# Schematic.net
KiCad netlist of a schematic drawn in Altium Designer
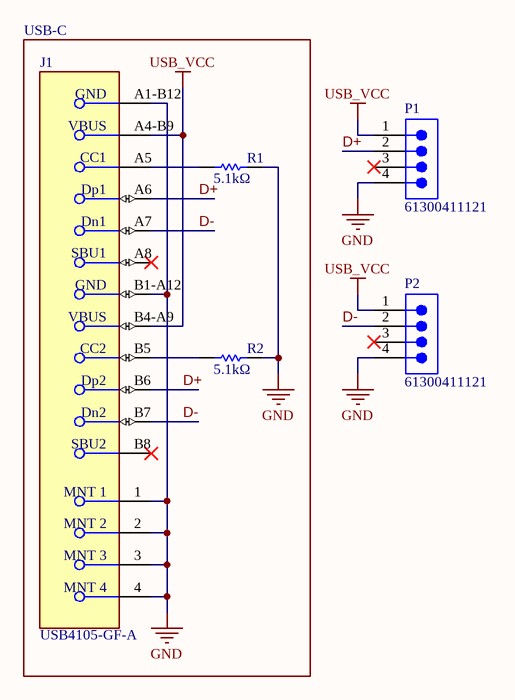
[diagram p0: Schematic.SchDoc]

(export (version "E")
  (design (tool "Eeschema 10.0.6"))
  (components
    (comp (ref "J1")
      (value "USB4105-GF-A")
      (footprint "FP-USB4105-GF-A-MFG")
      (description "CONN RCPT USB2.0 TYPEC 5A")
      (fields
        (field (name "MANUFACTURER") "GCT")
        (field (name "OCTOPART") "https://octopart.com/usb4105-gf-a-gct-106627878")
      )
      (libsource (lib "Altium Content Vault") (part "e7c17a616881a82b79941196b4bec10"))
    )
    (comp (ref "P1")
      (value "61300411121")
      (footprint "61300411121")
      (libsource (lib "Altium Content Vault") (part "Header_Male_1R_04P"))
    )
    (comp (ref "P2")
      (value "61300411121")
      (footprint "61300411121")
      (libsource (lib "Altium Content Vault") (part "Header_Male_1R_04P"))
    )
    (comp (ref "R1")
      (value "5.1kΩ")
      (footprint "RESC3116X65X40LL10T20")
      (fields (field (name "MANUFACTURER") "Yageo") (field (name "PART NUMBER") "RC1206JR-075K1L"))
      (libsource (lib "Altium Content Vault") (part "RES"))
    )
    (comp (ref "R2")
      (value "5.1kΩ")
      (footprint "RESC3116X65X40LL10T20")
      (fields (field (name "MANUFACTURER") "Yageo") (field (name "PART NUMBER") "RC1206JR-075K1L"))
      (libsource (lib "Altium Content Vault") (part "RES"))
    )
  )
  (nets
    (net (code "1") (name "/D+") (class "Default")
      (node (ref "J1") (pin "A6") (pinfunction "Dp1_A6") (pintype "bidirectional"))
      (node (ref "J1") (pin "B6") (pinfunction "Dp2_B6") (pintype "bidirectional"))
      (node (ref "P1") (pin "2") (pinfunction "2_2") (pintype "passive"))
    )
    (net (code "2") (name "/D-") (class "Default")
      (node (ref "J1") (pin "A7") (pinfunction "Dn1_A7") (pintype "bidirectional"))
      (node (ref "J1") (pin "B7") (pinfunction "Dn2_B7") (pintype "bidirectional"))
      (node (ref "P2") (pin "2") (pinfunction "2_2") (pintype "passive"))
    )
    (net (code "3") (name "GND") (class "Default")
      (node (ref "J1") (pin "1") (pinfunction "MNT_1_1") (pintype "power_in"))
      (node (ref "J1") (pin "2") (pinfunction "MNT_2_2") (pintype "power_in"))
      (node (ref "J1") (pin "3") (pinfunction "MNT_3_3") (pintype "power_in"))
      (node (ref "J1") (pin "4") (pinfunction "MNT_4_4") (pintype "power_in"))
      (node (ref "J1") (pin "A1-B12") (pinfunction "GND_A1-B12") (pintype "power_in"))
      (node (ref "J1") (pin "B1-A12") (pinfunction "GND_B1-A12") (pintype "bidirectional"))
      (node (ref "P1") (pin "4") (pinfunction "4_4") (pintype "passive"))
      (node (ref "P2") (pin "4") (pinfunction "4_4") (pintype "passive"))
      (node (ref "R1") (pin "2") (pinfunction "2_2") (pintype "passive"))
      (node (ref "R2") (pin "2") (pinfunction "2_2") (pintype "passive"))
    )
    (net (code "4") (name "Net-(J1-CC1)") (class "Default")
      (node (ref "J1") (pin "A5") (pinfunction "CC1_A5") (pintype "power_in"))
      (node (ref "R1") (pin "1") (pinfunction "1_1") (pintype "passive"))
    )
    (net (code "5") (name "Net-(J1-CC2)") (class "Default")
      (node (ref "J1") (pin "B5") (pinfunction "CC2_B5") (pintype "bidirectional"))
      (node (ref "R2") (pin "1") (pinfunction "1_1") (pintype "passive"))
    )
    (net (code "6") (name "USB_VCC") (class "Default")
      (node (ref "J1") (pin "A4-B9") (pinfunction "VBUS_A4-B9") (pintype "power_in"))
      (node (ref "J1") (pin "B4-A9") (pinfunction "VBUS_B4-A9") (pintype "bidirectional"))
      (node (ref "P1") (pin "1") (pinfunction "1_1") (pintype "passive"))
      (node (ref "P2") (pin "1") (pinfunction "1_1") (pintype "passive"))
    )
    (net (code "7") (name "unconnected-(J1-SBU1-PadA8)") (class "Default")
      (node (ref "J1") (pin "A8") (pinfunction "SBU1_A8") (pintype "bidirectional+no_connect"))
    )
    (net (code "8") (name "unconnected-(J1-SBU2-PadB8)") (class "Default")
      (node (ref "J1") (pin "B8") (pinfunction "SBU2_B8") (pintype "power_in+no_connect"))
    )
    (net (code "9") (name "unconnected-(P1-Pad3)") (class "Default")
      (node (ref "P1") (pin "3") (pinfunction "3_3") (pintype "passive+no_connect"))
    )
    (net (code "10") (name "unconnected-(P2-Pad3)") (class "Default")
      (node (ref "P2") (pin "3") (pinfunction "3_3") (pintype "passive+no_connect"))
    )
  )
)
